# TAH_BOARD_VER_3_0.net
KiCad netlist of a schematic drawn in EAGLE
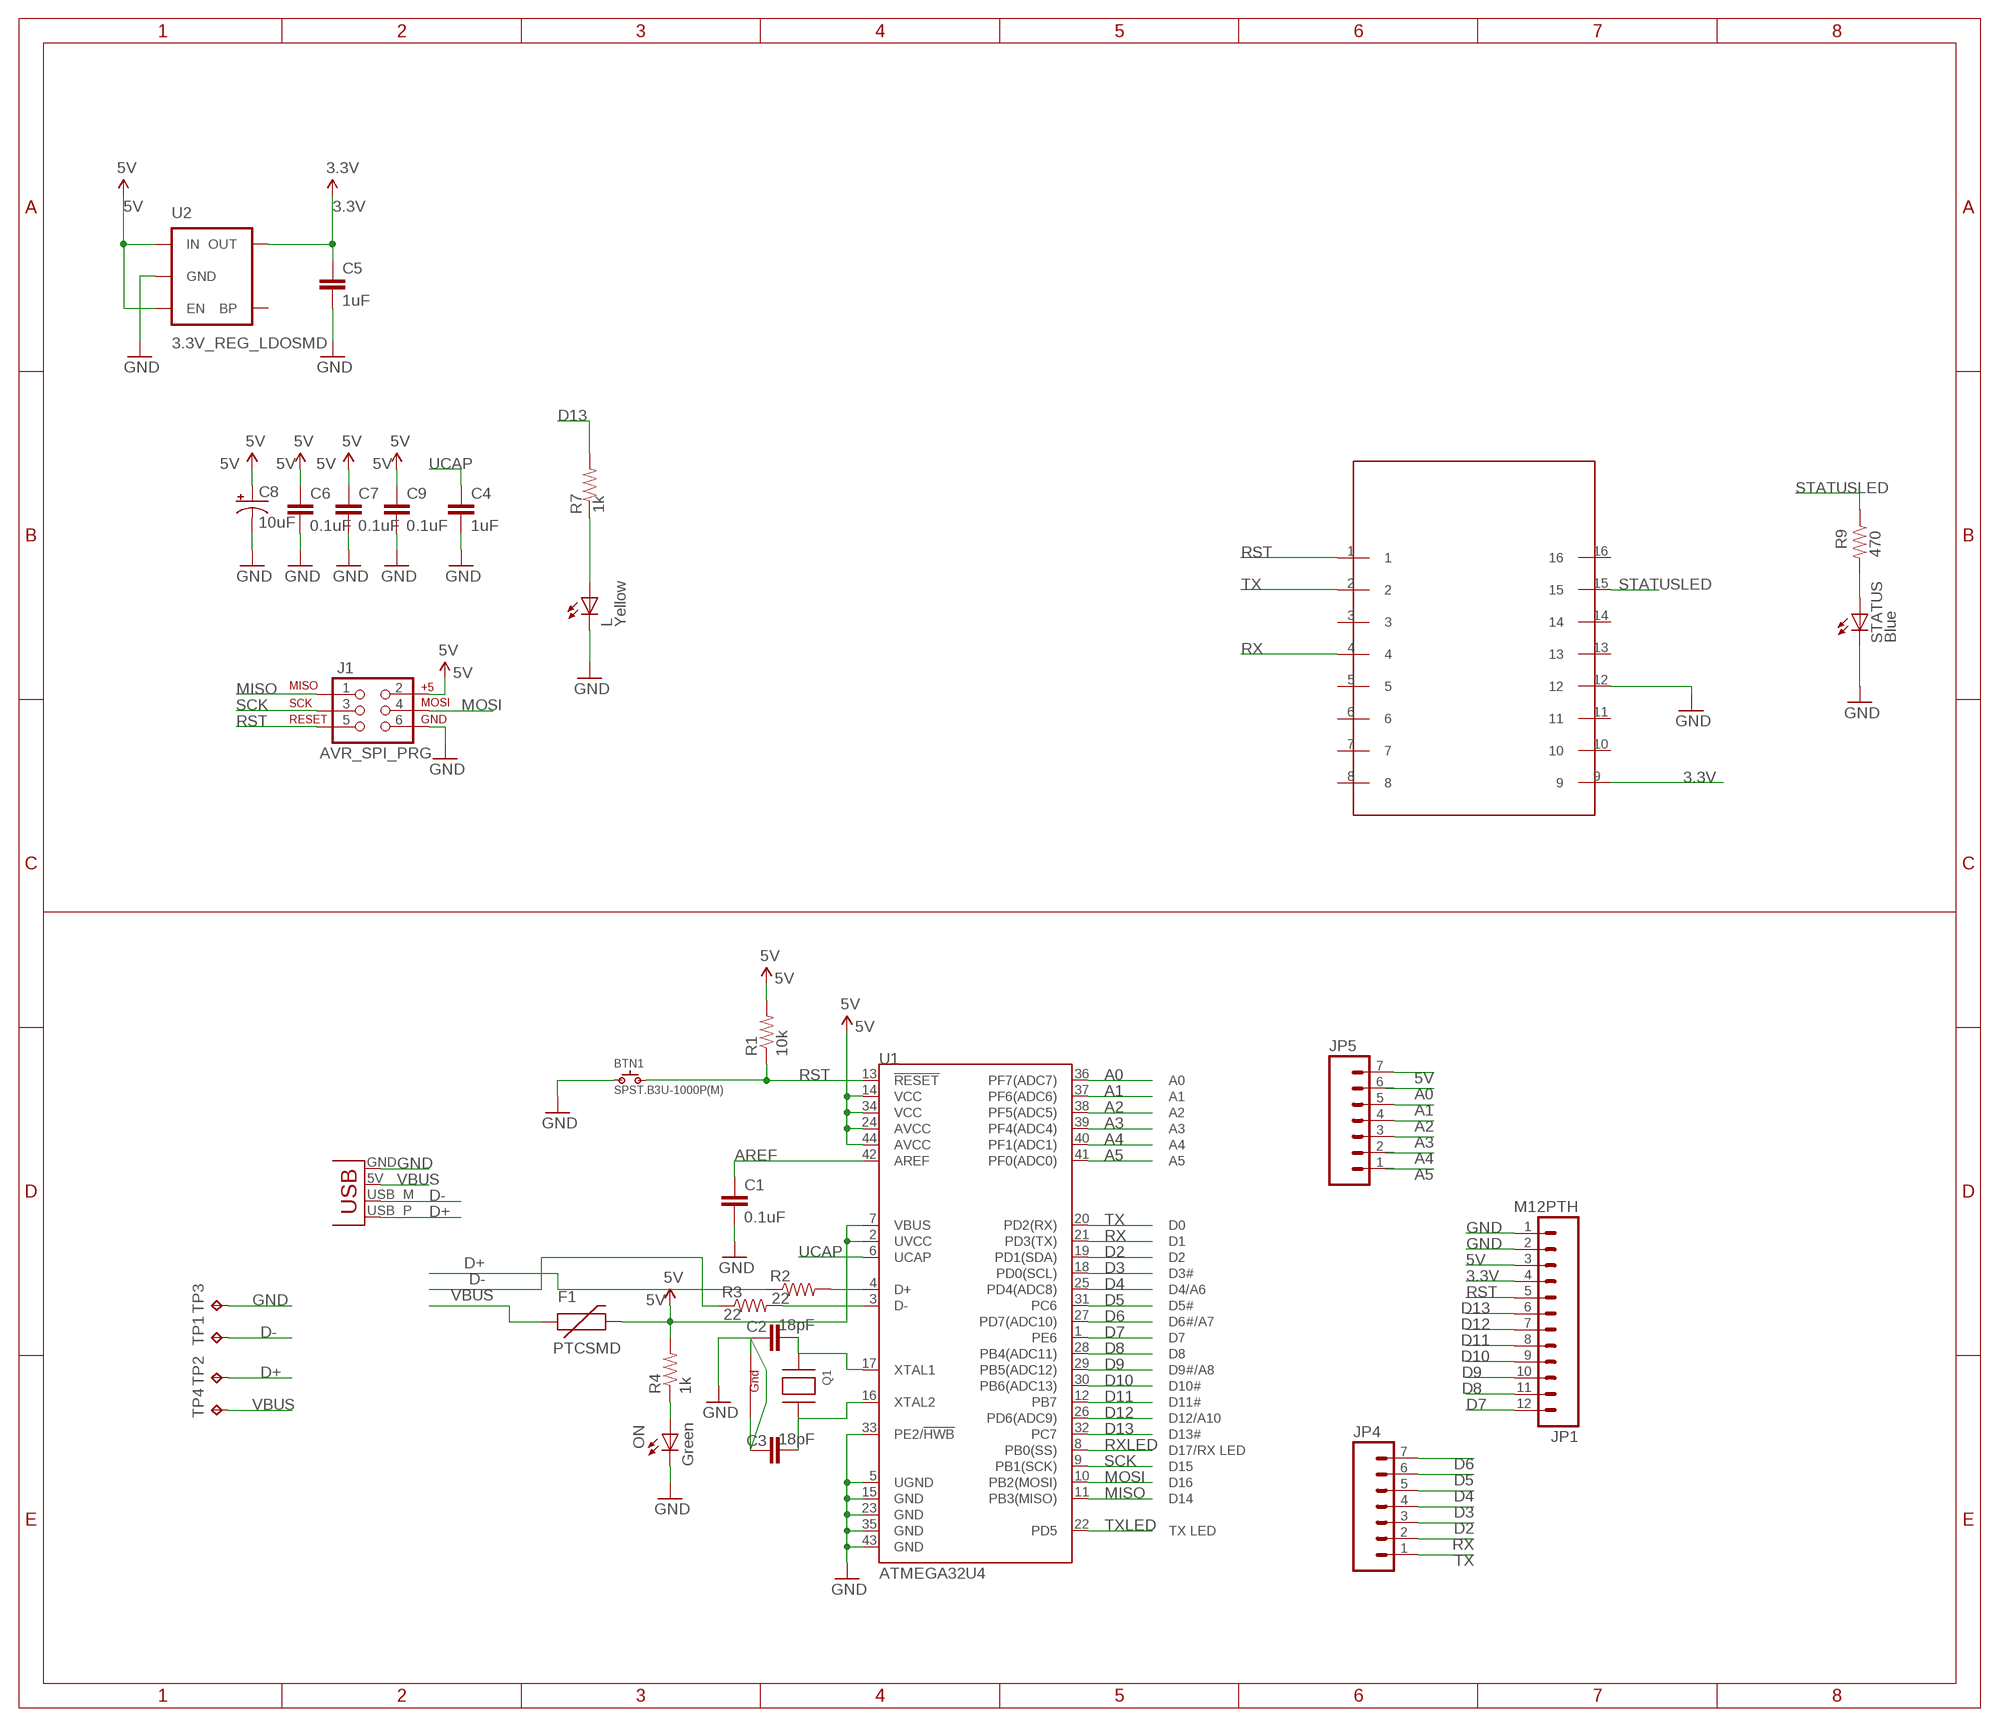
[diagram p0: schematic, sheet 1]

(export (version "E")
  (design (tool "Eeschema 10.0.6"))
  (components
    (comp (ref "BLE")
      (value "HM-11HM11")
      (footprint "eagle-import:BC05B-SMD")
      (libsource (lib "eagle-import") (part "HM-11HM11"))
    )
    (comp (ref "BTN1")
      (value "SPST.B3U-1000P(M)")
      (footprint "eagle-import:B3U-1000P(M)")
      (libsource (lib "eagle-import") (part "SPST.B3U-1000P(M)"))
    )
    (comp (ref "C1")
      (value "0.1uF")
      (footprint "eagle-import:1206")
      (libsource (lib "eagle-import") (part "2.2UF-CERCAP-10009"))
    )
    (comp (ref "C2")
      (value "18pF")
      (footprint "eagle-import:1206")
      (libsource (lib "eagle-import") (part "2.2UF-CERCAP-10009"))
    )
    (comp (ref "C3")
      (value "18pF")
      (footprint "eagle-import:1206")
      (libsource (lib "eagle-import") (part "2.2UF-CERCAP-10009"))
    )
    (comp (ref "C4")
      (value "1uF")
      (footprint "eagle-import:1206")
      (libsource (lib "eagle-import") (part "2.2UF-CERCAP-10009"))
    )
    (comp (ref "C5")
      (value "1uF")
      (footprint "eagle-import:1206")
      (libsource (lib "eagle-import") (part "2.2UF-CERCAP-10009"))
    )
    (comp (ref "C6")
      (value "0.1uF")
      (footprint "eagle-import:1206")
      (libsource (lib "eagle-import") (part "2.2UF-CERCAP-10009"))
    )
    (comp (ref "C7")
      (value "0.1uF")
      (footprint "eagle-import:1206")
      (libsource (lib "eagle-import") (part "2.2UF-CERCAP-10009"))
    )
    (comp (ref "C8")
      (value "10uF")
      (footprint "eagle-import:EIA3216")
      (libsource (lib "eagle-import") (part "CAP_POL1206"))
    )
    (comp (ref "C9")
      (value "0.1uF")
      (footprint "eagle-import:1206")
      (libsource (lib "eagle-import") (part "2.2UF-CERCAP-10009"))
    )
    (comp (ref "F1")
      (value "PTCSMD")
      (footprint "eagle-import:PTC-1206")
      (libsource (lib "eagle-import") (part "PTCSMD"))
    )
    (comp (ref "J1")
      (value "AVR_SPI_PRG")
      (footprint "eagle-import:2X3")
      (libsource (lib "eagle-import") (part "AVR_SPI_PRG_6PTH"))
    )
    (comp (ref "JP1")
      (value "M12PTH")
      (footprint "eagle-import:1X12")
      (libsource (lib "eagle-import") (part "M12PTH"))
    )
    (comp (ref "JP2")
      (value "USBPCB")
      (footprint "eagle-import:USB-A-PCB")
      (libsource (lib "eagle-import") (part "USBPCB"))
    )
    (comp (ref "JP4")
      (value "M07")
      (footprint "eagle-import:1X07")
      (libsource (lib "eagle-import") (part "M07"))
    )
    (comp (ref "JP5")
      (value "M07")
      (footprint "eagle-import:1X07")
      (libsource (lib "eagle-import") (part "M07"))
    )
    (comp (ref "L")
      (value "Yellow")
      (footprint "eagle-import:1206")
      (libsource (lib "eagle-import") (part "LEDSMT1206"))
    )
    (comp (ref "ON")
      (value "Green")
      (footprint "eagle-import:1206")
      (libsource (lib "eagle-import") (part "LEDSMT1206"))
    )
    (comp (ref "Q1")
      (value "XTAL-4-3225")
      (footprint "eagle-import:NX3225")
      (libsource (lib "eagle-import") (part "XTAL-4-3225"))
    )
    (comp (ref "R1")
      (value "10k")
      (footprint "eagle-import:1206")
      (libsource (lib "eagle-import") (part "RESISTOR1206"))
    )
    (comp (ref "R2")
      (value "22")
      (footprint "eagle-import:1206")
      (libsource (lib "eagle-import") (part "RESISTOR1206"))
    )
    (comp (ref "R3")
      (value "22")
      (footprint "eagle-import:1206")
      (libsource (lib "eagle-import") (part "RESISTOR1206"))
    )
    (comp (ref "R4")
      (value "1k")
      (footprint "eagle-import:1206")
      (libsource (lib "eagle-import") (part "RESISTOR1206"))
    )
    (comp (ref "R7")
      (value "1k")
      (footprint "eagle-import:1206")
      (libsource (lib "eagle-import") (part "RESISTOR1206"))
    )
    (comp (ref "R9")
      (value "470")
      (footprint "eagle-import:1206")
      (libsource (lib "eagle-import") (part "RESISTOR1206"))
    )
    (comp (ref "STATUS")
      (value "Blue")
      (footprint "eagle-import:1206")
      (libsource (lib "eagle-import") (part "LEDSMT1206"))
    )
    (comp (ref "TP1")
      (value "TPTP11SQ")
      (footprint "eagle-import:TP11SQ")
      (libsource (lib "eagle-import") (part "TPTP11SQ"))
    )
    (comp (ref "TP2")
      (value "TPTP11SQ")
      (footprint "eagle-import:TP11SQ")
      (libsource (lib "eagle-import") (part "TPTP11SQ"))
    )
    (comp (ref "TP3")
      (value "TPTP11SQ")
      (footprint "eagle-import:TP11SQ")
      (libsource (lib "eagle-import") (part "TPTP11SQ"))
    )
    (comp (ref "TP4")
      (value "TPTP11SQ")
      (footprint "eagle-import:TP11SQ")
      (libsource (lib "eagle-import") (part "TPTP11SQ"))
    )
    (comp (ref "U1")
      (value "ATMEGA32U4")
      (footprint "eagle-import:SPARKFUN-DIGITALIC_TQFP44")
      (libsource (lib "eagle-import") (part "ATMEGA32U4TQFP"))
    )
    (comp (ref "U2")
      (value "3.3V_REG_LDOSMD")
      (footprint "eagle-import:SOT23-5")
      (libsource (lib "eagle-import") (part "V_REG_LDOSMD"))
    )
  )
  (nets
    (net (code "1") (name "/A0") (class "Default")
      (node (ref "JP5") (pin "6") (pinfunction "6_6") (pintype "passive"))
      (node (ref "U1") (pin "36") (pinfunction "PF7(ADC7)_36") (pintype "bidirectional"))
    )
    (net (code "2") (name "/A1") (class "Default")
      (node (ref "JP5") (pin "5") (pinfunction "5_5") (pintype "passive"))
      (node (ref "U1") (pin "37") (pinfunction "PF6(ADC6)_37") (pintype "bidirectional"))
    )
    (net (code "3") (name "/A2") (class "Default")
      (node (ref "JP5") (pin "4") (pinfunction "4_4") (pintype "passive"))
      (node (ref "U1") (pin "38") (pinfunction "PF5(ADC5)_38") (pintype "bidirectional"))
    )
    (net (code "4") (name "/A3") (class "Default")
      (node (ref "JP5") (pin "3") (pinfunction "3_3") (pintype "passive"))
      (node (ref "U1") (pin "39") (pinfunction "PF4(ADC4)_39") (pintype "bidirectional"))
    )
    (net (code "5") (name "/A4") (class "Default")
      (node (ref "JP5") (pin "2") (pinfunction "2_2") (pintype "passive"))
      (node (ref "U1") (pin "40") (pinfunction "PF1(ADC1)_40") (pintype "bidirectional"))
    )
    (net (code "6") (name "/A5") (class "Default")
      (node (ref "JP5") (pin "1") (pinfunction "1_1") (pintype "passive"))
      (node (ref "U1") (pin "41") (pinfunction "PF0(ADC0)_41") (pintype "bidirectional"))
    )
    (net (code "7") (name "/AREF") (class "Default")
      (node (ref "C1") (pin "1") (pinfunction "1_1") (pintype "passive"))
      (node (ref "U1") (pin "42") (pinfunction "AREF_42") (pintype "bidirectional"))
    )
    (net (code "8") (name "/D+") (class "Default")
      (node (ref "JP2") (pin "USB_P") (pinfunction "D+_USB_P") (pintype "bidirectional"))
      (node (ref "R2") (pin "1") (pinfunction "1_1") (pintype "passive"))
      (node (ref "TP2") (pin "TP") (pinfunction "TP_TP") (pintype "input"))
    )
    (net (code "9") (name "/D-") (class "Default")
      (node (ref "JP2") (pin "USB_M") (pinfunction "D-_USB_M") (pintype "bidirectional"))
      (node (ref "R3") (pin "1") (pinfunction "1_1") (pintype "passive"))
      (node (ref "TP1") (pin "TP") (pinfunction "TP_TP") (pintype "input"))
    )
    (net (code "10") (name "/D2") (class "Default")
      (node (ref "JP4") (pin "3") (pinfunction "3_3") (pintype "passive"))
      (node (ref "U1") (pin "19") (pinfunction "PD1(SDA)_19") (pintype "bidirectional"))
    )
    (net (code "11") (name "/D3") (class "Default")
      (node (ref "JP4") (pin "4") (pinfunction "4_4") (pintype "passive"))
      (node (ref "U1") (pin "18") (pinfunction "PD0(SCL)_18") (pintype "bidirectional"))
    )
    (net (code "12") (name "/D4") (class "Default")
      (node (ref "JP4") (pin "5") (pinfunction "5_5") (pintype "passive"))
      (node (ref "U1") (pin "25") (pinfunction "PD4(ADC8)_25") (pintype "bidirectional"))
    )
    (net (code "13") (name "/D5") (class "Default")
      (node (ref "JP4") (pin "6") (pinfunction "6_6") (pintype "passive"))
      (node (ref "U1") (pin "31") (pinfunction "PC6_31") (pintype "bidirectional"))
    )
    (net (code "14") (name "/D6") (class "Default")
      (node (ref "JP4") (pin "7") (pinfunction "7_7") (pintype "passive"))
      (node (ref "U1") (pin "27") (pinfunction "PD7(ADC10)_27") (pintype "bidirectional"))
    )
    (net (code "15") (name "/D7") (class "Default")
      (node (ref "JP1") (pin "12") (pinfunction "12_12") (pintype "passive"))
      (node (ref "U1") (pin "1") (pinfunction "PE6_1") (pintype "bidirectional"))
    )
    (net (code "16") (name "/D8") (class "Default")
      (node (ref "JP1") (pin "11") (pinfunction "11_11") (pintype "passive"))
      (node (ref "U1") (pin "28") (pinfunction "PB4(ADC11)_28") (pintype "bidirectional"))
    )
    (net (code "17") (name "/D9") (class "Default")
      (node (ref "JP1") (pin "10") (pinfunction "10_10") (pintype "passive"))
      (node (ref "U1") (pin "29") (pinfunction "PB5(ADC12)_29") (pintype "bidirectional"))
    )
    (net (code "18") (name "/D10") (class "Default")
      (node (ref "JP1") (pin "9") (pinfunction "9_9") (pintype "passive"))
      (node (ref "U1") (pin "30") (pinfunction "PB6(ADC13)_30") (pintype "bidirectional"))
    )
    (net (code "19") (name "/D11") (class "Default")
      (node (ref "JP1") (pin "8") (pinfunction "8_8") (pintype "passive"))
      (node (ref "U1") (pin "12") (pinfunction "PB7_12") (pintype "bidirectional"))
    )
    (net (code "20") (name "/D12") (class "Default")
      (node (ref "JP1") (pin "7") (pinfunction "7_7") (pintype "passive"))
      (node (ref "U1") (pin "26") (pinfunction "PD6(ADC9)_26") (pintype "bidirectional"))
    )
    (net (code "21") (name "/D13") (class "Default")
      (node (ref "JP1") (pin "6") (pinfunction "6_6") (pintype "passive"))
      (node (ref "R7") (pin "2") (pinfunction "2_2") (pintype "passive"))
      (node (ref "U1") (pin "32") (pinfunction "PC7_32") (pintype "bidirectional"))
    )
    (net (code "22") (name "/MISO") (class "Default")
      (node (ref "J1") (pin "1") (pinfunction "1_1") (pintype "passive"))
      (node (ref "U1") (pin "11") (pinfunction "PB3(MISO)_11") (pintype "bidirectional"))
    )
    (net (code "23") (name "/MOSI") (class "Default")
      (node (ref "J1") (pin "4") (pinfunction "4_4") (pintype "passive"))
      (node (ref "U1") (pin "10") (pinfunction "PB2(MOSI)_10") (pintype "bidirectional"))
    )
    (net (code "24") (name "/RST") (class "Default")
      (node (ref "BLE") (pin "1") (pinfunction "1_1") (pintype "bidirectional"))
      (node (ref "BTN1") (pin "2") (pinfunction "2_2") (pintype "bidirectional"))
      (node (ref "J1") (pin "5") (pinfunction "5_5") (pintype "passive"))
      (node (ref "JP1") (pin "5") (pinfunction "5_5") (pintype "passive"))
      (node (ref "R1") (pin "1") (pinfunction "1_1") (pintype "passive"))
      (node (ref "U1") (pin "13") (pinfunction "~{RESET}_13") (pintype "bidirectional"))
    )
    (net (code "25") (name "/RX") (class "Default")
      (node (ref "BLE") (pin "4") (pinfunction "4_4") (pintype "bidirectional"))
      (node (ref "JP4") (pin "2") (pinfunction "2_2") (pintype "passive"))
      (node (ref "U1") (pin "21") (pinfunction "PD3(TX)_21") (pintype "bidirectional"))
    )
    (net (code "26") (name "/RXLED") (class "Default")
      (node (ref "U1") (pin "8") (pinfunction "PB0(SS)_8") (pintype "bidirectional"))
    )
    (net (code "27") (name "/SCK") (class "Default")
      (node (ref "J1") (pin "3") (pinfunction "3_3") (pintype "passive"))
      (node (ref "U1") (pin "9") (pinfunction "PB1(SCK)_9") (pintype "bidirectional"))
    )
    (net (code "28") (name "/STATUSLED") (class "Default")
      (node (ref "BLE") (pin "15") (pinfunction "15_15") (pintype "bidirectional"))
      (node (ref "R9") (pin "1") (pinfunction "1_1") (pintype "passive"))
    )
    (net (code "29") (name "/TX") (class "Default")
      (node (ref "BLE") (pin "2") (pinfunction "2_2") (pintype "bidirectional"))
      (node (ref "JP4") (pin "1") (pinfunction "1_1") (pintype "passive"))
      (node (ref "U1") (pin "20") (pinfunction "PD2(RX)_20") (pintype "bidirectional"))
    )
    (net (code "30") (name "/TXLED") (class "Default")
      (node (ref "U1") (pin "22") (pinfunction "PD5_22") (pintype "bidirectional"))
    )
    (net (code "31") (name "/UCAP") (class "Default")
      (node (ref "C4") (pin "1") (pinfunction "1_1") (pintype "passive"))
      (node (ref "U1") (pin "6") (pinfunction "UCAP_6") (pintype "bidirectional"))
    )
    (net (code "32") (name "/VBUS") (class "Default")
      (node (ref "F1") (pin "1") (pinfunction "1_1") (pintype "bidirectional"))
      (node (ref "JP2") (pin "5V") (pinfunction "VBUS_5V") (pintype "bidirectional"))
      (node (ref "TP4") (pin "TP") (pinfunction "TP_TP") (pintype "input"))
    )
    (net (code "33") (name "3.3V") (class "Default")
      (node (ref "BLE") (pin "9") (pinfunction "9_9") (pintype "bidirectional"))
      (node (ref "C5") (pin "1") (pinfunction "1_1") (pintype "passive"))
      (node (ref "JP1") (pin "4") (pinfunction "4_4") (pintype "passive"))
      (node (ref "U2") (pin "5") (pinfunction "OUT_5") (pintype "passive"))
    )
    (net (code "34") (name "5V") (class "Default")
      (node (ref "C6") (pin "1") (pinfunction "1_1") (pintype "passive"))
      (node (ref "C7") (pin "1") (pinfunction "1_1") (pintype "passive"))
      (node (ref "C8") (pin "A") (pinfunction "+_A") (pintype "passive"))
      (node (ref "C9") (pin "1") (pinfunction "1_1") (pintype "passive"))
      (node (ref "F1") (pin "2") (pinfunction "2_2") (pintype "bidirectional"))
      (node (ref "J1") (pin "2") (pinfunction "2_2") (pintype "passive"))
      (node (ref "JP1") (pin "3") (pinfunction "3_3") (pintype "passive"))
      (node (ref "JP5") (pin "7") (pinfunction "7_7") (pintype "passive"))
      (node (ref "R1") (pin "2") (pinfunction "2_2") (pintype "passive"))
      (node (ref "R4") (pin "2") (pinfunction "2_2") (pintype "passive"))
      (node (ref "U1") (pin "14") (pinfunction "VCC_14") (pintype "bidirectional"))
      (node (ref "U1") (pin "2") (pinfunction "UVCC_2") (pintype "bidirectional"))
      (node (ref "U1") (pin "24") (pinfunction "AVCC_24") (pintype "bidirectional"))
      (node (ref "U1") (pin "34") (pinfunction "VCC_34") (pintype "bidirectional"))
      (node (ref "U1") (pin "44") (pinfunction "AVCC_44") (pintype "bidirectional"))
      (node (ref "U1") (pin "7") (pinfunction "VBUS_7") (pintype "bidirectional"))
      (node (ref "U2") (pin "1") (pinfunction "IN_1") (pintype "input"))
      (node (ref "U2") (pin "3") (pinfunction "EN_3") (pintype "input"))
    )
    (net (code "35") (name "GND") (class "Default")
      (node (ref "BLE") (pin "12") (pinfunction "12_12") (pintype "bidirectional"))
      (node (ref "BTN1") (pin "1") (pinfunction "1_1") (pintype "bidirectional"))
      (node (ref "C1") (pin "2") (pinfunction "2_2") (pintype "passive"))
      (node (ref "C2") (pin "1") (pinfunction "1_1") (pintype "passive"))
      (node (ref "C3") (pin "1") (pinfunction "1_1") (pintype "passive"))
      (node (ref "C4") (pin "2") (pinfunction "2_2") (pintype "passive"))
      (node (ref "C5") (pin "2") (pinfunction "2_2") (pintype "passive"))
      (node (ref "C6") (pin "2") (pinfunction "2_2") (pintype "passive"))
      (node (ref "C7") (pin "2") (pinfunction "2_2") (pintype "passive"))
      (node (ref "C8") (pin "C") (pinfunction "-_C") (pintype "passive"))
      (node (ref "C9") (pin "2") (pinfunction "2_2") (pintype "passive"))
      (node (ref "J1") (pin "6") (pinfunction "6_6") (pintype "passive"))
      (node (ref "JP1") (pin "1") (pinfunction "1_1") (pintype "passive"))
      (node (ref "JP1") (pin "2") (pinfunction "2_2") (pintype "passive"))
      (node (ref "JP2") (pin "GND") (pinfunction "GND_GND") (pintype "bidirectional"))
      (node (ref "L") (pin "C") (pinfunction "C_C") (pintype "passive"))
      (node (ref "ON") (pin "C") (pinfunction "C_C") (pintype "passive"))
      (node (ref "Q1") (pin "2") (pinfunction "G2_2") (pintype "power_in"))
      (node (ref "Q1") (pin "4") (pinfunction "G1_4") (pintype "power_in"))
      (node (ref "STATUS") (pin "C") (pinfunction "C_C") (pintype "passive"))
      (node (ref "TP3") (pin "TP") (pinfunction "TP_TP") (pintype "input"))
      (node (ref "U1") (pin "15") (pinfunction "GND_15") (pintype "bidirectional"))
      (node (ref "U1") (pin "23") (pinfunction "GND_23") (pintype "bidirectional"))
      (node (ref "U1") (pin "33") (pinfunction "PE2/~{HWB}_33") (pintype "bidirectional"))
      (node (ref "U1") (pin "35") (pinfunction "GND_35") (pintype "bidirectional"))
      (node (ref "U1") (pin "43") (pinfunction "GND_43") (pintype "bidirectional"))
      (node (ref "U1") (pin "5") (pinfunction "UGND_5") (pintype "bidirectional"))
      (node (ref "U2") (pin "2") (pinfunction "GND_2") (pintype "input"))
    )
    (net (code "36") (name "Net-(L-PadA)") (class "Default")
      (node (ref "L") (pin "A") (pinfunction "A_A") (pintype "passive"))
      (node (ref "R7") (pin "1") (pinfunction "1_1") (pintype "passive"))
    )
    (net (code "37") (name "Net-(ON-PadA)") (class "Default")
      (node (ref "ON") (pin "A") (pinfunction "A_A") (pintype "passive"))
      (node (ref "R4") (pin "1") (pinfunction "1_1") (pintype "passive"))
    )
    (net (code "38") (name "Net-(Q1-X1)") (class "Default")
      (node (ref "C2") (pin "2") (pinfunction "2_2") (pintype "passive"))
      (node (ref "Q1") (pin "1") (pinfunction "X1_1") (pintype "bidirectional"))
      (node (ref "U1") (pin "17") (pinfunction "XTAL1_17") (pintype "bidirectional"))
    )
    (net (code "39") (name "Net-(Q1-X2)") (class "Default")
      (node (ref "C3") (pin "2") (pinfunction "2_2") (pintype "passive"))
      (node (ref "Q1") (pin "3") (pinfunction "X2_3") (pintype "bidirectional"))
      (node (ref "U1") (pin "16") (pinfunction "XTAL2_16") (pintype "bidirectional"))
    )
    (net (code "40") (name "Net-(R9-Pad2)") (class "Default")
      (node (ref "R9") (pin "2") (pinfunction "2_2") (pintype "passive"))
      (node (ref "STATUS") (pin "A") (pinfunction "A_A") (pintype "passive"))
    )
    (net (code "41") (name "Net-(U1-D+)") (class "Default")
      (node (ref "R2") (pin "2") (pinfunction "2_2") (pintype "passive"))
      (node (ref "U1") (pin "4") (pinfunction "D+_4") (pintype "bidirectional"))
    )
    (net (code "42") (name "Net-(U1-D-)") (class "Default")
      (node (ref "R3") (pin "2") (pinfunction "2_2") (pintype "passive"))
      (node (ref "U1") (pin "3") (pinfunction "D-_3") (pintype "bidirectional"))
    )
    (net (code "43") (name "unconnected-(BLE-Pad3)") (class "Default")
      (node (ref "BLE") (pin "3") (pinfunction "3_3") (pintype "bidirectional"))
    )
    (net (code "44") (name "unconnected-(BLE-Pad5)") (class "Default")
      (node (ref "BLE") (pin "5") (pinfunction "5_5") (pintype "bidirectional"))
    )
    (net (code "45") (name "unconnected-(BLE-Pad6)") (class "Default")
      (node (ref "BLE") (pin "6") (pinfunction "6_6") (pintype "bidirectional"))
    )
    (net (code "46") (name "unconnected-(BLE-Pad7)") (class "Default")
      (node (ref "BLE") (pin "7") (pinfunction "7_7") (pintype "bidirectional"))
    )
    (net (code "47") (name "unconnected-(BLE-Pad8)") (class "Default")
      (node (ref "BLE") (pin "8") (pinfunction "8_8") (pintype "bidirectional"))
    )
    (net (code "48") (name "unconnected-(BLE-Pad10)") (class "Default")
      (node (ref "BLE") (pin "10") (pinfunction "10_10") (pintype "bidirectional"))
    )
    (net (code "49") (name "unconnected-(BLE-Pad11)") (class "Default")
      (node (ref "BLE") (pin "11") (pinfunction "11_11") (pintype "bidirectional"))
    )
    (net (code "50") (name "unconnected-(BLE-Pad13)") (class "Default")
      (node (ref "BLE") (pin "13") (pinfunction "13_13") (pintype "bidirectional"))
    )
    (net (code "51") (name "unconnected-(BLE-Pad14)") (class "Default")
      (node (ref "BLE") (pin "14") (pinfunction "14_14") (pintype "bidirectional"))
    )
    (net (code "52") (name "unconnected-(BLE-Pad16)") (class "Default")
      (node (ref "BLE") (pin "16") (pinfunction "16_16") (pintype "bidirectional"))
    )
    (net (code "53") (name "unconnected-(U2-BP-Pad4)") (class "Default")
      (node (ref "U2") (pin "4") (pinfunction "BP_4") (pintype "input"))
    )
  )
)
